# ETD555_Project_Schematic.net
KiCad netlist of a schematic drawn in EAGLE
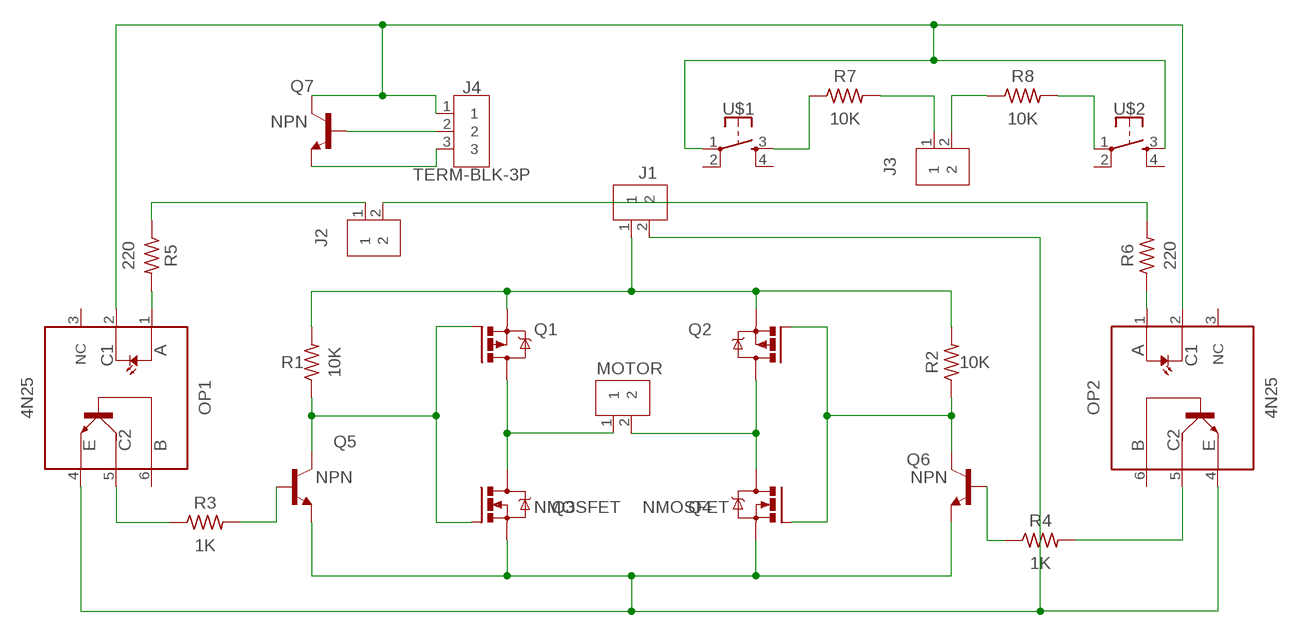
[diagram p0: schematic, sheet 1]

(export (version "E")
  (design (tool "Eeschema 10.0.6"))
  (components
    (comp (ref "J1")
      (value "TERM-BLK-2P")
      (footprint "eagle-import:TERMBLK_508-2N")
      (fields (field (name "MANUFACTURER") "TE Connectivity AMP Connectors") (field (name "MPN") "282837-2"))
      (libsource (lib "eagle-import") (part "2828XX-2282837-2"))
    )
    (comp (ref "J2")
      (value "TERM-BLK-2P")
      (footprint "eagle-import:TERMBLK_508-2N")
      (fields (field (name "MANUFACTURER") "TE Connectivity AMP Connectors") (field (name "MPN") "282837-2"))
      (libsource (lib "eagle-import") (part "2828XX-2282837-2"))
    )
    (comp (ref "J3")
      (value "TERM-BLK-2P")
      (footprint "eagle-import:TERMBLK_508-2N")
      (fields (field (name "MANUFACTURER") "TE Connectivity AMP Connectors") (field (name "MPN") "282837-2"))
      (libsource (lib "eagle-import") (part "2828XX-2282837-2"))
    )
    (comp (ref "J4")
      (value "TERM-BLK-3P")
      (footprint "eagle-import:TERMBLK_254-3N")
      (fields (field (name "MANUFACTURER") "TE Connectivity AMP Connectors") (field (name "MPN") "282834-3"))
      (libsource (lib "eagle-import") (part "2828XX-3282834-3"))
    )
    (comp (ref "MOTOR")
      (value "TERM-BLK-2P")
      (footprint "eagle-import:TERMBLK_508-2N")
      (fields (field (name "MANUFACTURER") "TE Connectivity AMP Connectors") (field (name "MPN") "282837-2"))
      (libsource (lib "eagle-import") (part "2828XX-2282837-2"))
    )
    (comp (ref "OP1")
      (value "4N25")
      (footprint "eagle-import:DIP762W60P254L712H480Q6B")
      (fields (field (name "MANUFACTURER") "Vishay"))
      (libsource (lib "eagle-import") (part "4N25"))
    )
    (comp (ref "OP2")
      (value "4N25")
      (footprint "eagle-import:DIP762W60P254L712H480Q6B")
      (fields (field (name "MANUFACTURER") "Vishay"))
      (libsource (lib "eagle-import") (part "4N25"))
    )
    (comp (ref "Q1")
      (value "PMOSFET")
      (footprint "eagle-import:TO220BV")
      (libsource (lib "eagle-import") (part "PMOSFET_TO220_"))
    )
    (comp (ref "Q2")
      (value "PMOSFET")
      (footprint "eagle-import:TO220BV")
      (libsource (lib "eagle-import") (part "PMOSFET_TO220_"))
    )
    (comp (ref "Q3")
      (value "NMOSFET")
      (footprint "eagle-import:TO220BV")
      (libsource (lib "eagle-import") (part "NMOSFETTO220_"))
    )
    (comp (ref "Q4")
      (value "NMOSFET")
      (footprint "eagle-import:TO220BV")
      (libsource (lib "eagle-import") (part "NMOSFETTO220_"))
    )
    (comp (ref "Q5")
      (value "NPN")
      (footprint "eagle-import:TO92")
      (libsource (lib "eagle-import") (part "NPNTO92-EBC_"))
    )
    (comp (ref "Q6")
      (value "NPN")
      (footprint "eagle-import:TO92")
      (libsource (lib "eagle-import") (part "NPNTO92-EBC_"))
    )
    (comp (ref "Q7")
      (value "NPN")
      (footprint "eagle-import:TO92")
      (libsource (lib "eagle-import") (part "NPNTO92-EBC_"))
    )
    (comp (ref "R1")
      (value "10K")
      (footprint "eagle-import:RESAD724W46L381D178B")
      (libsource (lib "eagle-import") (part "R-USAXIAL-7.2MM-PITCH_"))
    )
    (comp (ref "R2")
      (value "10K")
      (footprint "eagle-import:RESAD724W46L381D178B")
      (libsource (lib "eagle-import") (part "R-USAXIAL-7.2MM-PITCH_"))
    )
    (comp (ref "R3")
      (value "1K")
      (footprint "eagle-import:RESAD724W46L381D178B")
      (libsource (lib "eagle-import") (part "R-USAXIAL-7.2MM-PITCH_"))
    )
    (comp (ref "R4")
      (value "1K")
      (footprint "eagle-import:RESAD724W46L381D178B")
      (libsource (lib "eagle-import") (part "R-USAXIAL-7.2MM-PITCH_"))
    )
    (comp (ref "R5")
      (value "220")
      (footprint "eagle-import:RESAD724W46L381D178B")
      (libsource (lib "eagle-import") (part "R-USAXIAL-7.2MM-PITCH_"))
    )
    (comp (ref "R6")
      (value "220")
      (footprint "eagle-import:RESAD724W46L381D178B")
      (libsource (lib "eagle-import") (part "R-USAXIAL-7.2MM-PITCH_"))
    )
    (comp (ref "R7")
      (value "10K")
      (footprint "eagle-import:RESAD724W46L381D178B")
      (libsource (lib "eagle-import") (part "R-USAXIAL-7.2MM-PITCH_"))
    )
    (comp (ref "R8")
      (value "10K")
      (footprint "eagle-import:RESAD724W46L381D178B")
      (libsource (lib "eagle-import") (part "R-USAXIAL-7.2MM-PITCH_"))
    )
    (comp (ref "U$1")
      (value "SWITCH_MOMENTARY")
      (footprint "eagle-import:SWITCH-MOMENTARY-PTH-6.5MM")
      (libsource (lib "eagle-import") (part "SWITCH_MOMENTARY"))
    )
    (comp (ref "U$2")
      (value "SWITCH_MOMENTARY")
      (footprint "eagle-import:SWITCH-MOMENTARY-PTH-6.5MM")
      (libsource (lib "eagle-import") (part "SWITCH_MOMENTARY"))
    )
  )
  (nets
    (net (code "1") (name "Net-(J1-Pad1)") (class "Default")
      (node (ref "J1") (pin "1") (pinfunction "1_1") (pintype "bidirectional"))
      (node (ref "Q1") (pin "S") (pinfunction "S_S") (pintype "passive"))
      (node (ref "Q2") (pin "S") (pinfunction "S_S") (pintype "passive"))
      (node (ref "R1") (pin "2") (pinfunction "2_2") (pintype "passive"))
      (node (ref "R2") (pin "2") (pinfunction "2_2") (pintype "passive"))
    )
    (net (code "2") (name "Net-(J2-Pad1)") (class "Default")
      (node (ref "J2") (pin "1") (pinfunction "1_1") (pintype "bidirectional"))
      (node (ref "R5") (pin "1") (pinfunction "1_1") (pintype "passive"))
    )
    (net (code "3") (name "Net-(J2-Pad2)") (class "Default")
      (node (ref "J2") (pin "2") (pinfunction "2_2") (pintype "bidirectional"))
      (node (ref "R6") (pin "2") (pinfunction "2_2") (pintype "passive"))
    )
    (net (code "4") (name "Net-(J3-Pad1)") (class "Default")
      (node (ref "J3") (pin "1") (pinfunction "1_1") (pintype "bidirectional"))
      (node (ref "R7") (pin "2") (pinfunction "2_2") (pintype "passive"))
    )
    (net (code "5") (name "Net-(J3-Pad2)") (class "Default")
      (node (ref "J3") (pin "2") (pinfunction "2_2") (pintype "bidirectional"))
      (node (ref "R8") (pin "1") (pinfunction "1_1") (pintype "passive"))
    )
    (net (code "6") (name "Net-(MOTOR-Pad1)") (class "Default")
      (node (ref "MOTOR") (pin "1") (pinfunction "1_1") (pintype "bidirectional"))
      (node (ref "Q1") (pin "D") (pinfunction "D_D") (pintype "passive"))
      (node (ref "Q3") (pin "D") (pinfunction "D_D") (pintype "passive"))
    )
    (net (code "7") (name "Net-(MOTOR-Pad2)") (class "Default")
      (node (ref "MOTOR") (pin "2") (pinfunction "2_2") (pintype "bidirectional"))
      (node (ref "Q2") (pin "D") (pinfunction "D_D") (pintype "passive"))
      (node (ref "Q4") (pin "D") (pinfunction "D_D") (pintype "passive"))
    )
    (net (code "8") (name "Net-(OP1-A)") (class "Default")
      (node (ref "OP1") (pin "1") (pinfunction "A_1") (pintype "passive"))
      (node (ref "R5") (pin "2") (pinfunction "2_2") (pintype "passive"))
    )
    (net (code "9") (name "Net-(OP1-C1)") (class "Default")
      (node (ref "J4") (pin "1") (pinfunction "1_1") (pintype "bidirectional"))
      (node (ref "OP1") (pin "2") (pinfunction "C1_2") (pintype "passive"))
      (node (ref "OP2") (pin "2") (pinfunction "C1_2") (pintype "passive"))
      (node (ref "Q7") (pin "3") (pinfunction "C_3") (pintype "passive"))
      (node (ref "U$1") (pin "1") (pinfunction "1_1") (pintype "passive"))
      (node (ref "U$2") (pin "3") (pinfunction "3_3") (pintype "passive"))
    )
    (net (code "10") (name "Net-(OP1-C2)") (class "Default")
      (node (ref "OP1") (pin "5") (pinfunction "C2_5") (pintype "passive"))
      (node (ref "R3") (pin "1") (pinfunction "1_1") (pintype "passive"))
    )
    (net (code "11") (name "Net-(OP1-E)") (class "Default")
      (node (ref "J1") (pin "2") (pinfunction "2_2") (pintype "bidirectional"))
      (node (ref "OP1") (pin "4") (pinfunction "E_4") (pintype "passive"))
      (node (ref "OP2") (pin "4") (pinfunction "E_4") (pintype "passive"))
      (node (ref "Q3") (pin "S") (pinfunction "S_S") (pintype "passive"))
      (node (ref "Q4") (pin "S") (pinfunction "S_S") (pintype "passive"))
      (node (ref "Q5") (pin "1") (pinfunction "E_1") (pintype "passive"))
      (node (ref "Q6") (pin "1") (pinfunction "E_1") (pintype "passive"))
    )
    (net (code "12") (name "Net-(OP2-A)") (class "Default")
      (node (ref "OP2") (pin "1") (pinfunction "A_1") (pintype "passive"))
      (node (ref "R6") (pin "1") (pinfunction "1_1") (pintype "passive"))
    )
    (net (code "13") (name "Net-(OP2-C2)") (class "Default")
      (node (ref "OP2") (pin "5") (pinfunction "C2_5") (pintype "passive"))
      (node (ref "R4") (pin "2") (pinfunction "2_2") (pintype "passive"))
    )
    (net (code "14") (name "Net-(Q5-B)") (class "Default")
      (node (ref "Q5") (pin "2") (pinfunction "B_2") (pintype "passive"))
      (node (ref "R3") (pin "2") (pinfunction "2_2") (pintype "passive"))
    )
    (net (code "15") (name "Net-(Q5-C)") (class "Default")
      (node (ref "Q1") (pin "G") (pinfunction "G_G") (pintype "passive"))
      (node (ref "Q3") (pin "G") (pinfunction "G_G") (pintype "passive"))
      (node (ref "Q5") (pin "3") (pinfunction "C_3") (pintype "passive"))
      (node (ref "R1") (pin "1") (pinfunction "1_1") (pintype "passive"))
    )
    (net (code "16") (name "Net-(Q6-B)") (class "Default")
      (node (ref "Q6") (pin "2") (pinfunction "B_2") (pintype "passive"))
      (node (ref "R4") (pin "1") (pinfunction "1_1") (pintype "passive"))
    )
    (net (code "17") (name "Net-(Q6-C)") (class "Default")
      (node (ref "Q2") (pin "G") (pinfunction "G_G") (pintype "passive"))
      (node (ref "Q4") (pin "G") (pinfunction "G_G") (pintype "passive"))
      (node (ref "Q6") (pin "3") (pinfunction "C_3") (pintype "passive"))
      (node (ref "R2") (pin "1") (pinfunction "1_1") (pintype "passive"))
    )
    (net (code "18") (name "Net-(Q7-B)") (class "Default")
      (node (ref "J4") (pin "2") (pinfunction "2_2") (pintype "bidirectional"))
      (node (ref "Q7") (pin "2") (pinfunction "B_2") (pintype "passive"))
    )
    (net (code "19") (name "Net-(Q7-E)") (class "Default")
      (node (ref "J4") (pin "3") (pinfunction "3_3") (pintype "bidirectional"))
      (node (ref "Q7") (pin "1") (pinfunction "E_1") (pintype "passive"))
    )
    (net (code "20") (name "Net-(R7-Pad1)") (class "Default")
      (node (ref "R7") (pin "1") (pinfunction "1_1") (pintype "passive"))
      (node (ref "U$1") (pin "3") (pinfunction "3_3") (pintype "passive"))
    )
    (net (code "21") (name "Net-(R8-Pad2)") (class "Default")
      (node (ref "R8") (pin "2") (pinfunction "2_2") (pintype "passive"))
      (node (ref "U$2") (pin "1") (pinfunction "1_1") (pintype "passive"))
    )
    (net (code "22") (name "unconnected-(OP1-B-Pad6)") (class "Default")
      (node (ref "OP1") (pin "6") (pinfunction "B_6") (pintype "passive"))
    )
    (net (code "23") (name "unconnected-(OP1-NC-Pad3)") (class "Default")
      (node (ref "OP1") (pin "3") (pinfunction "NC_3") (pintype "no_connect"))
    )
    (net (code "24") (name "unconnected-(OP2-B-Pad6)") (class "Default")
      (node (ref "OP2") (pin "6") (pinfunction "B_6") (pintype "passive"))
    )
    (net (code "25") (name "unconnected-(OP2-NC-Pad3)") (class "Default")
      (node (ref "OP2") (pin "3") (pinfunction "NC_3") (pintype "no_connect"))
    )
    (net (code "26") (name "unconnected-(U$1-Pad2)") (class "Default")
      (node (ref "U$1") (pin "2") (pinfunction "2_2") (pintype "passive"))
    )
    (net (code "27") (name "unconnected-(U$1-Pad4)") (class "Default")
      (node (ref "U$1") (pin "4") (pinfunction "4_4") (pintype "passive"))
    )
    (net (code "28") (name "unconnected-(U$2-Pad2)") (class "Default")
      (node (ref "U$2") (pin "2") (pinfunction "2_2") (pintype "passive"))
    )
    (net (code "29") (name "unconnected-(U$2-Pad4)") (class "Default")
      (node (ref "U$2") (pin "4") (pinfunction "4_4") (pintype "passive"))
    )
  )
)
